# DCDC-BASE-X2B.net
KiCad netlist of a schematic drawn in EAGLE
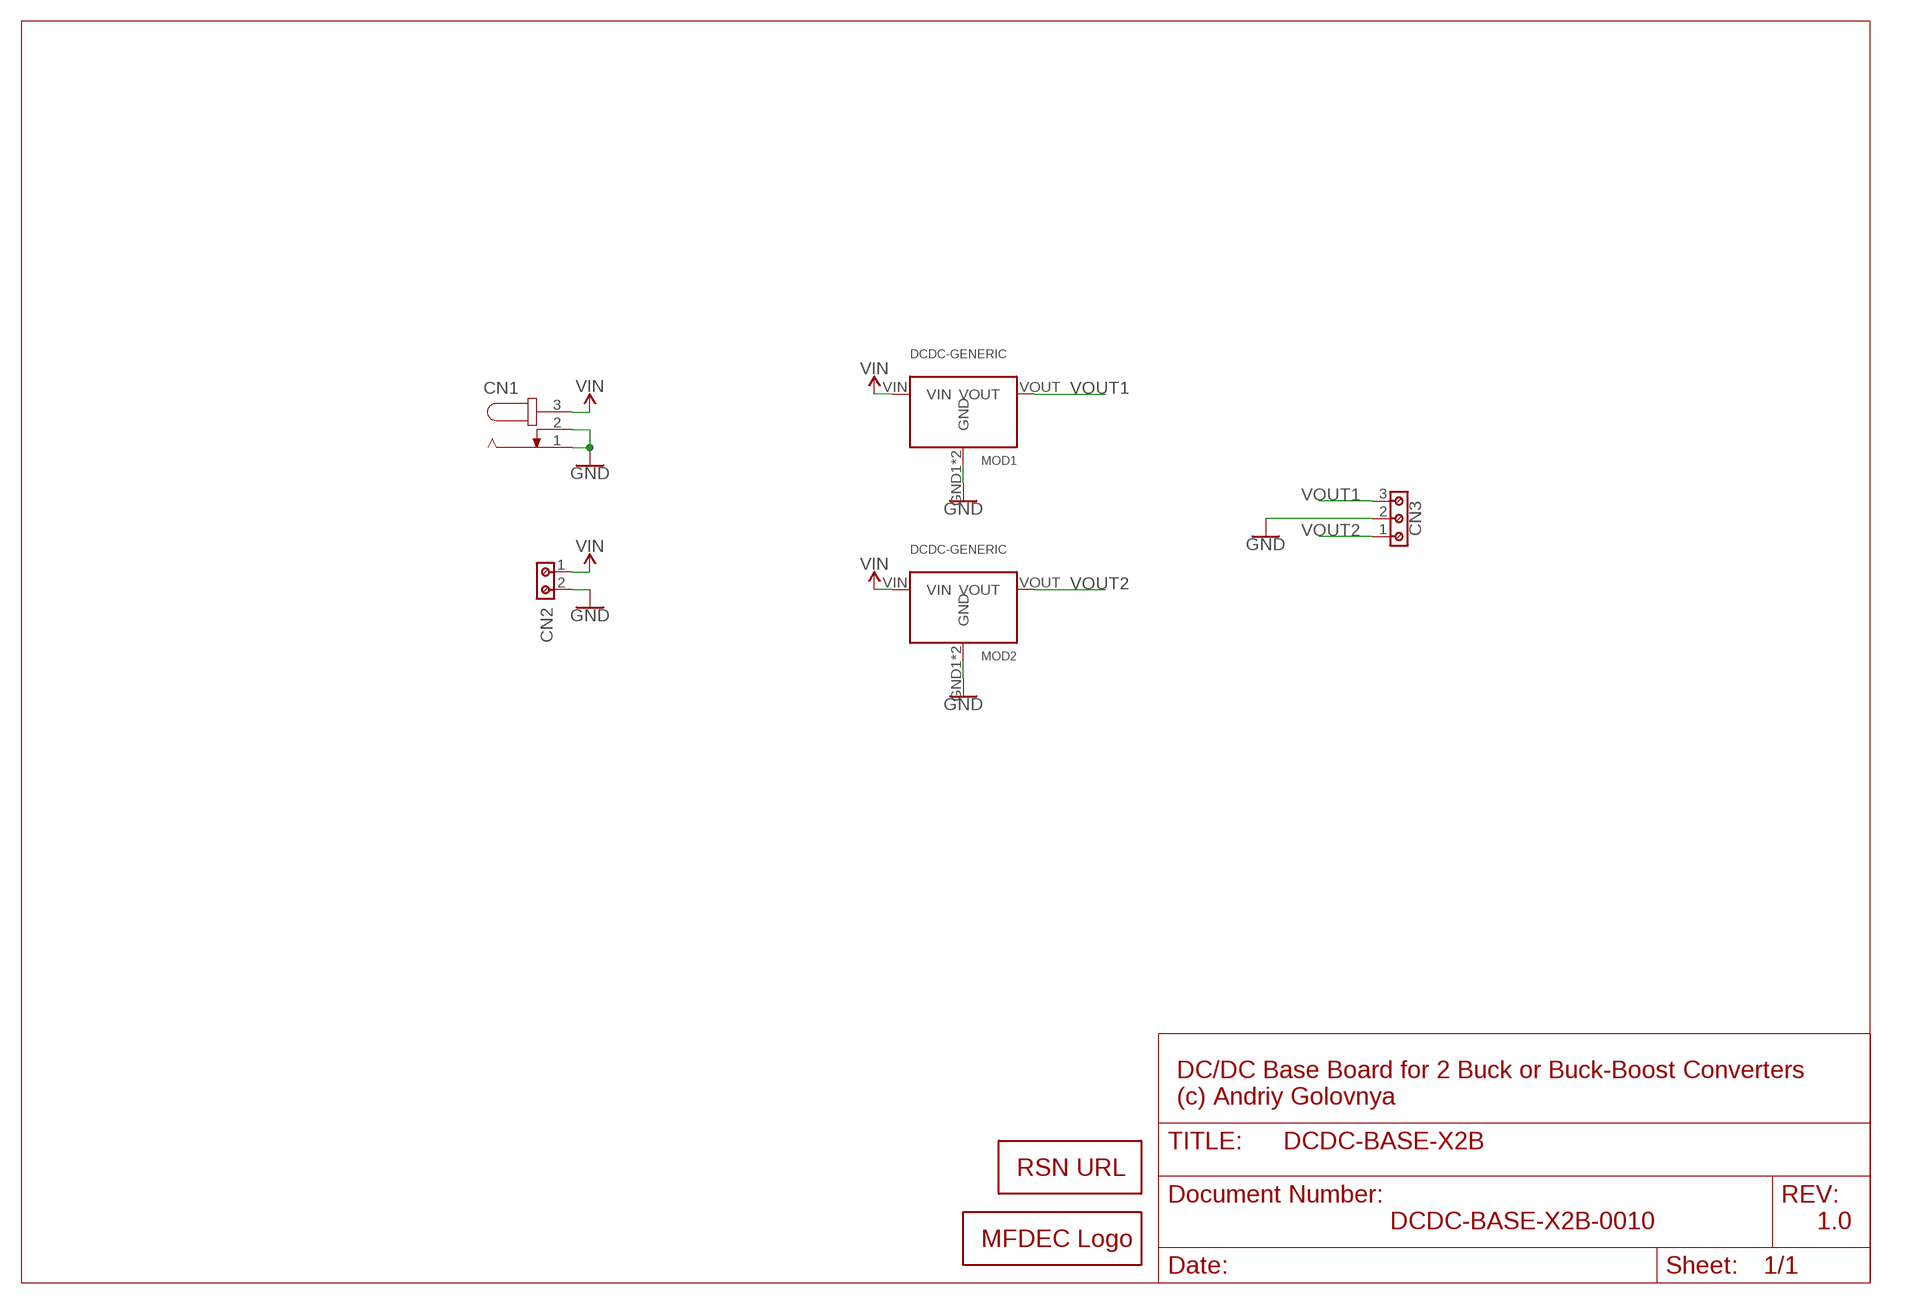
[diagram p0: schematic, sheet 1]

(export (version "E")
  (design (tool "Eeschema 10.0.6"))
  (components
    (comp (ref "CN1")
      (value "JACK-PLUG1")
      (footprint "eagle-import:SPC4078")
      (libsource (lib "eagle-import") (part "JACK-PLUG1"))
    )
    (comp (ref "CN2")
      (value "691213510002")
      (footprint "eagle-import:691213510002")
      (libsource (lib "eagle-import") (part "691213510002"))
    )
    (comp (ref "CN3")
      (value "691213510003")
      (footprint "eagle-import:691213510003")
      (libsource (lib "eagle-import") (part "691213510003"))
    )
    (comp (ref "LOGO1")
      (value "RSNURL_QR_8MM")
      (footprint "eagle-import:RSNURL_QR_8MM")
      (libsource (lib "eagle-import") (part "RSNURL_QR_8MM"))
    )
    (comp (ref "LOGO2")
      (value "MFDECLOGO_L_10MM")
      (footprint "eagle-import:MFDEC_L_10MM")
      (libsource (lib "eagle-import") (part "MFDECLOGO_L_10MM"))
    )
    (comp (ref "MOD1")
      (value "DCDC-GENERIC")
      (footprint "eagle-import:DCDC-BOARD")
      (libsource (lib "eagle-import") (part "DCDC-GENERIC"))
    )
    (comp (ref "MOD2")
      (value "DCDC-GENERIC")
      (footprint "eagle-import:DCDC-BOARD")
      (libsource (lib "eagle-import") (part "DCDC-GENERIC"))
    )
  )
  (nets
    (net (code "1") (name "/VOUT1") (class "Default")
      (node (ref "CN3") (pin "3") (pinfunction "3_3") (pintype "passive"))
      (node (ref "MOD1") (pin "VOUT") (pinfunction "VOUT_VOUT") (pintype "bidirectional"))
    )
    (net (code "2") (name "/VOUT2") (class "Default")
      (node (ref "CN3") (pin "1") (pinfunction "1_1") (pintype "passive"))
      (node (ref "MOD2") (pin "VOUT") (pinfunction "VOUT_VOUT") (pintype "bidirectional"))
    )
    (net (code "3") (name "GND") (class "Default")
      (node (ref "CN1") (pin "1") (pinfunction "1_1") (pintype "passive"))
      (node (ref "CN1") (pin "2") (pinfunction "2_2") (pintype "passive"))
      (node (ref "CN2") (pin "2") (pinfunction "2_2") (pintype "passive"))
      (node (ref "CN3") (pin "2") (pinfunction "2_2") (pintype "passive"))
      (node (ref "MOD1") (pin "GND1") (pinfunction "GND_GND1") (pintype "bidirectional"))
      (node (ref "MOD1") (pin "GND2") (pinfunction "GND_GND2") (pintype "bidirectional"))
      (node (ref "MOD2") (pin "GND1") (pinfunction "GND_GND1") (pintype "bidirectional"))
      (node (ref "MOD2") (pin "GND2") (pinfunction "GND_GND2") (pintype "bidirectional"))
    )
    (net (code "4") (name "VIN") (class "Default")
      (node (ref "CN1") (pin "3") (pinfunction "3_3") (pintype "passive"))
      (node (ref "CN2") (pin "1") (pinfunction "1_1") (pintype "passive"))
      (node (ref "MOD1") (pin "VIN") (pinfunction "VIN_VIN") (pintype "bidirectional"))
      (node (ref "MOD2") (pin "VIN") (pinfunction "VIN_VIN") (pintype "bidirectional"))
    )
  )
)
